# momentary_button.net
KiCad netlist of a schematic drawn in EAGLE
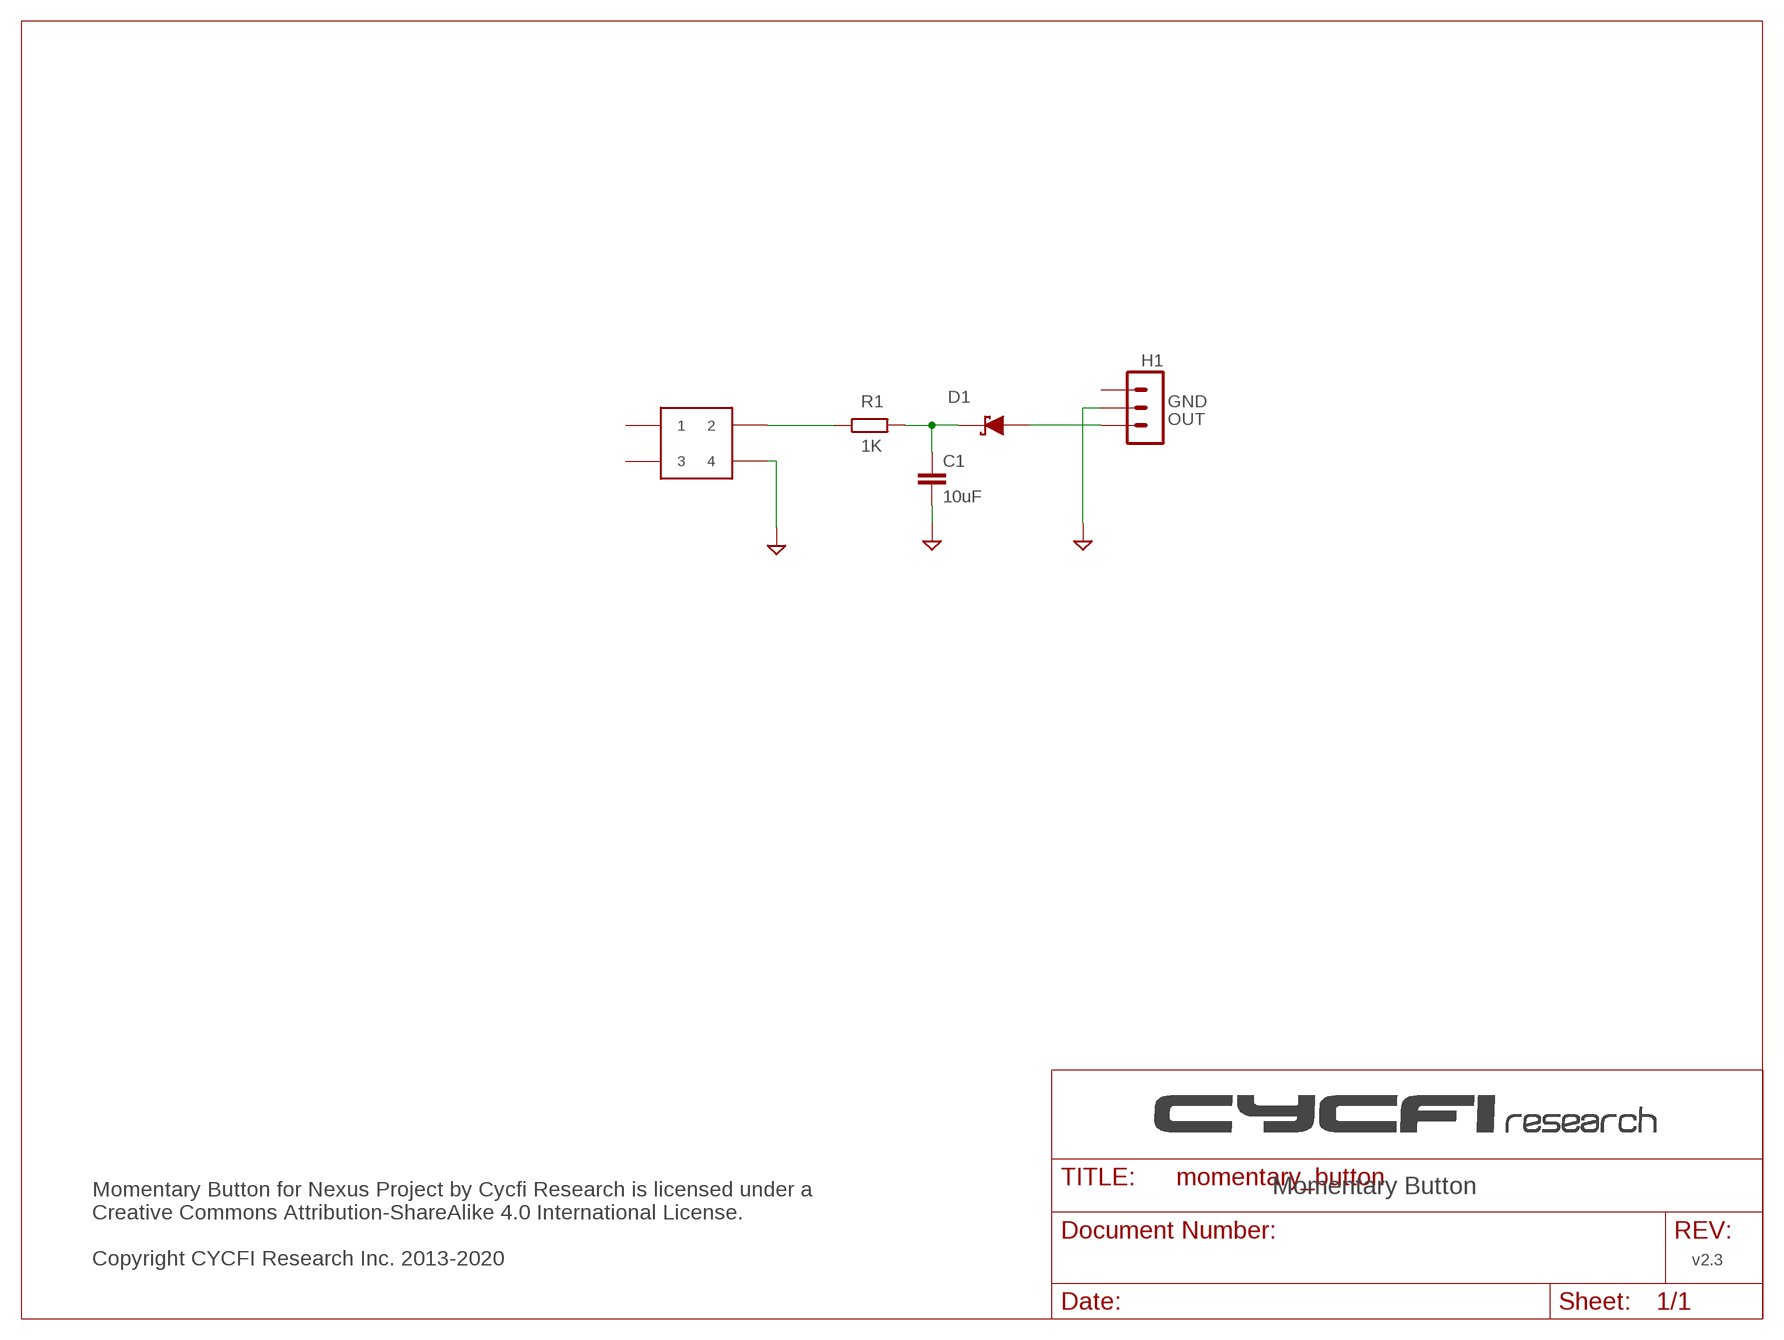
[diagram p0: schematic, sheet 1]

(export (version "E")
  (design (tool "Eeschema 10.0.6"))
  (components
    (comp (ref "C1")
      (value "10uF")
      (footprint "eagle-import:C0603")
      (libsource (lib "eagle-import") (part "C-EUC0603"))
    )
    (comp (ref "D1")
      (value "D_SCHOTTKYL")
      (footprint "eagle-import:SOD-323")
      (libsource (lib "eagle-import") (part "D_SCHOTTKYL"))
    )
    (comp (ref "H1")
      (value "3PIN-SMD-2.54MM")
      (footprint "eagle-import:3P-SMD-2.54MM")
      (libsource (lib "eagle-import") (part "3PIN-SMD-2.54MM"))
    )
    (comp (ref "R1")
      (value "1K")
      (footprint "eagle-import:R0402")
      (libsource (lib "eagle-import") (part "R-EU_R0402"))
    )
    (comp (ref "U$1")
      (value "TACT_6X6_SMD")
      (footprint "eagle-import:TACT_6X6_SMD")
      (libsource (lib "eagle-import") (part "TACT_6X6_SMD"))
    )
  )
  (nets
    (net (code "1") (name "GND") (class "Default")
      (node (ref "C1") (pin "2") (pinfunction "2_2") (pintype "passive"))
      (node (ref "H1") (pin "P$2") (pinfunction "2_P$2") (pintype "passive"))
      (node (ref "U$1") (pin "P$4") (pinfunction "4_P$4") (pintype "bidirectional"))
    )
    (net (code "2") (name "Net-(D1-A)") (class "Default")
      (node (ref "D1") (pin "1") (pinfunction "A_1") (pintype "passive"))
      (node (ref "H1") (pin "P$1") (pinfunction "1_P$1") (pintype "passive"))
    )
    (net (code "3") (name "Net-(D1-C)") (class "Default")
      (node (ref "C1") (pin "1") (pinfunction "1_1") (pintype "passive"))
      (node (ref "D1") (pin "2") (pinfunction "C_2") (pintype "passive"))
      (node (ref "R1") (pin "2") (pinfunction "2_2") (pintype "passive"))
    )
    (net (code "4") (name "Net-(U$1-2)") (class "Default")
      (node (ref "R1") (pin "1") (pinfunction "1_1") (pintype "passive"))
      (node (ref "U$1") (pin "P$2") (pinfunction "2_P$2") (pintype "bidirectional"))
    )
    (net (code "5") (name "unconnected-(H1-3-PadP$3)") (class "Default")
      (node (ref "H1") (pin "P$3") (pinfunction "3_P$3") (pintype "passive"))
    )
    (net (code "6") (name "unconnected-(U$1-1-PadP$1)") (class "Default")
      (node (ref "U$1") (pin "P$1") (pinfunction "1_P$1") (pintype "bidirectional"))
    )
    (net (code "7") (name "unconnected-(U$1-3-PadP$3)") (class "Default")
      (node (ref "U$1") (pin "P$3") (pinfunction "3_P$3") (pintype "bidirectional"))
    )
  )
)
